# User.net
KiCad netlist of a schematic drawn in Altium Designer
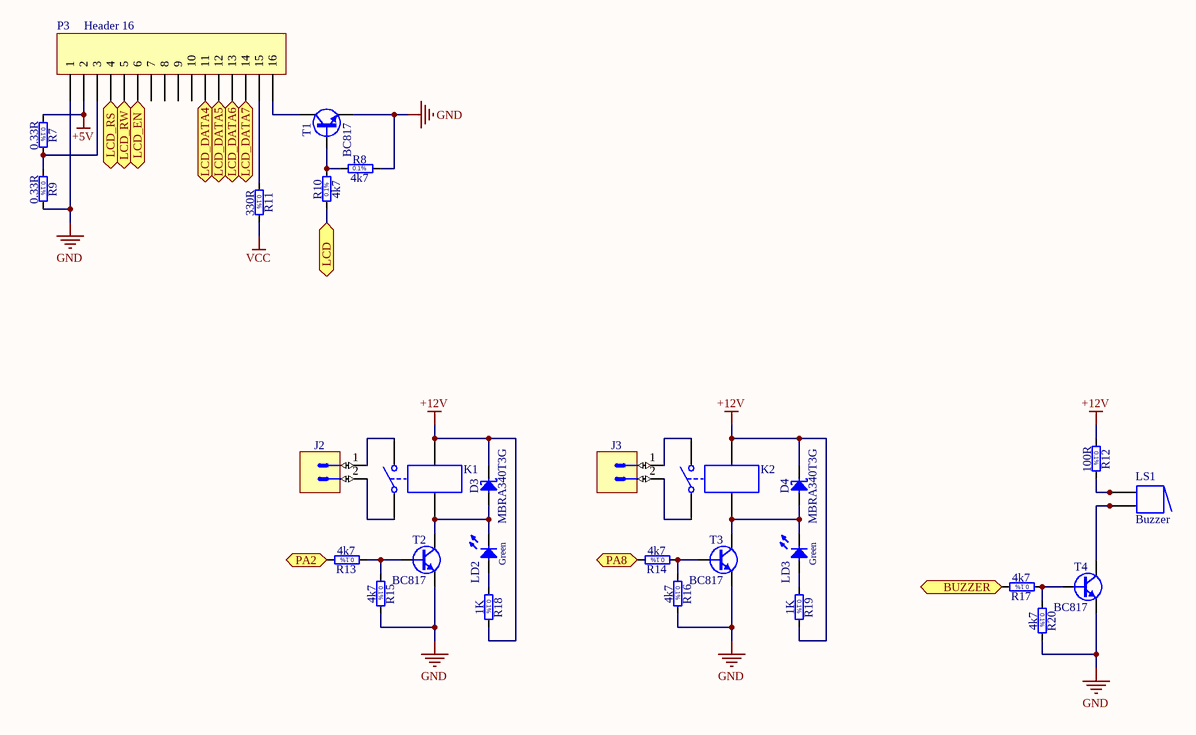
[diagram p0: User.SchDoc]

(export (version "E")
  (design (tool "Eeschema 10.0.6"))
  (components
    (comp (ref "D3")
      (value "MBRA340T3G")
      (footprint "DIOM5226X220N")
      (description "Schottky Diode")
      (fields
        (field (name "VOLTAGE") "40V")
        (field (name "POWER") "3A")
        (field (name "AUTHOR") "CERN DEM JLC")
      )
      (libsource (lib "ICs And Semiconductors") (part "Diode Schottky"))
    )
    (comp (ref "D4")
      (value "MBRA340T3G")
      (footprint "DIOM5226X220N")
      (description "Schottky Diode")
      (fields
        (field (name "VOLTAGE") "40V")
        (field (name "POWER") "3A")
        (field (name "AUTHOR") "CERN DEM JLC")
      )
      (libsource (lib "ICs And Semiconductors") (part "Diode Schottky"))
    )
    (comp (ref "J2")
      (value "~")
      (footprint "PHOENIX_1757242")
      (description "Connector 2 Male")
      (fields
        (field (name "PART NUMBER") "PHOENIX_1757242")
        (field (name "MANUFACTURER") "PHOENIX CONTACT")
        (field (name "AUTHOR") "CERN DEM JLC")
      )
      (libsource (lib "Connectors") (part "Connector 2 Male"))
    )
    (comp (ref "J3")
      (value "~")
      (footprint "PHOENIX_1757242")
      (description "Connector 2 Male")
      (fields
        (field (name "PART NUMBER") "PHOENIX_1757242")
        (field (name "MANUFACTURER") "PHOENIX CONTACT")
        (field (name "AUTHOR") "CERN DEM JLC")
      )
      (libsource (lib "Connectors") (part "Connector 2 Male"))
    )
    (comp (ref "K1")
      (value "Relay-SPST")
      (footprint "REL_FINDER_32.22.X.XXX.X300")
      (description "Single-Pole Single-Throw Relay")
      (fields (field (name "PUBLISHER") "Altium Limited"))
      (libsource (lib "Miscellaneous Devices") (part "Relay-SPST"))
    )
    (comp (ref "K2")
      (value "Relay-SPST")
      (footprint "REL_FINDER_32.22.X.XXX.X300")
      (description "Single-Pole Single-Throw Relay")
      (fields (field (name "PUBLISHER") "Altium Limited"))
      (libsource (lib "Miscellaneous Devices") (part "Relay-SPST"))
    )
    (comp (ref "LD2")
      (value "Green")
      (footprint "LED_OSRAM_LGR971")
      (description "LED Green 1C 2A")
      (fields
        (field (name "PART NUMBER") "LED_OSRAM_LGR971")
        (field (name "MANUFACTURER") "OSRAM")
        (field (name "AUTHOR") "CERN DEM JLC")
      )
      (libsource (lib "ICs And Semiconductors") (part "LED Green 1C 2A"))
    )
    (comp (ref "LD3")
      (value "Green")
      (footprint "LED_OSRAM_LGR971")
      (description "LED Green 1C 2A")
      (fields
        (field (name "PART NUMBER") "LED_OSRAM_LGR971")
        (field (name "MANUFACTURER") "OSRAM")
        (field (name "AUTHOR") "CERN DEM JLC")
      )
      (libsource (lib "ICs And Semiconductors") (part "LED Green 1C 2A"))
    )
    (comp (ref "LS1")
      (value "Buzzer")
      (footprint "ABSM-1574")
      (description "Magnetic Transducer Buzzer")
      (fields (field (name "PUBLISHER") "Altium Limited"))
      (libsource (lib "Miscellaneous Devices") (part "Buzzer"))
    )
    (comp (ref "P3")
      (value "Header 16")
      (footprint "HDR1X16")
      (description "Header, 16-Pin")
      (fields (field (name "PUBLISHER") "Altium Limited"))
      (libsource (lib "Miscellaneous Connectors") (part "Header 16"))
    )
    (comp (ref "R7")
      (value "0.33R")
      (footprint "RESC2012X60N")
      (description "Resistor - 0.1%")
      (fields
        (field (name "PART NUMBER") "R0805_1K1_0.1%_0.1W_10PPM")
        (field (name "POWER") "0.1W")
        (field (name "AUTHOR") "CERN DEM JLC")
      )
      (libsource (lib "Resistors") (part "Resistor - 0.1%"))
    )
    (comp (ref "R8")
      (value "4k7")
      (footprint "RESC2012X60N")
      (description "Resistor - 0.1%")
      (fields
        (field (name "PART NUMBER") "R0805_1K1_0.1%_0.1W_10PPM")
        (field (name "POWER") "0.1W")
        (field (name "AUTHOR") "CERN DEM JLC")
      )
      (libsource (lib "Resistors") (part "Resistor - 0.1%"))
    )
    (comp (ref "R9")
      (value "0.33R")
      (footprint "RESC2012X60N")
      (description "Resistor - 0.1%")
      (fields
        (field (name "PART NUMBER") "R0805_1K1_0.1%_0.1W_10PPM")
        (field (name "POWER") "0.1W")
        (field (name "AUTHOR") "CERN DEM JLC")
      )
      (libsource (lib "Resistors") (part "Resistor - 0.1%"))
    )
    (comp (ref "R10")
      (value "4k7")
      (footprint "RESC2012X60N")
      (description "Resistor - 0.1%")
      (fields
        (field (name "PART NUMBER") "R0805_1K1_0.1%_0.1W_10PPM")
        (field (name "POWER") "0.1W")
        (field (name "AUTHOR") "CERN DEM JLC")
      )
      (libsource (lib "Resistors") (part "Resistor - 0.1%"))
    )
    (comp (ref "R11")
      (value "330R")
      (footprint "RESC2012X60N")
      (description "Resistor - 0.1%")
      (fields
        (field (name "PART NUMBER") "R0805_1K1_0.1%_0.1W_10PPM")
        (field (name "POWER") "0.1W")
        (field (name "AUTHOR") "CERN DEM JLC")
      )
      (libsource (lib "Resistors") (part "Resistor - 0.1%"))
    )
    (comp (ref "R12")
      (value "100R")
      (footprint "RESC2012X60N")
      (description "Resistor - 0.1%")
      (fields
        (field (name "PART NUMBER") "R0805_1K1_0.1%_0.1W_10PPM")
        (field (name "POWER") "0.1W")
        (field (name "AUTHOR") "CERN DEM JLC")
      )
      (libsource (lib "Resistors") (part "Resistor - 0.1%"))
    )
    (comp (ref "R13")
      (value "4k7")
      (footprint "RESC2012X60N")
      (description "Resistor - 0.1%")
      (fields
        (field (name "PART NUMBER") "R0805_1K1_0.1%_0.1W_10PPM")
        (field (name "POWER") "0.1W")
        (field (name "AUTHOR") "CERN DEM JLC")
      )
      (libsource (lib "Resistors") (part "Resistor - 0.1%"))
    )
    (comp (ref "R14")
      (value "4k7")
      (footprint "RESC2012X60N")
      (description "Resistor - 0.1%")
      (fields
        (field (name "PART NUMBER") "R0805_1K1_0.1%_0.1W_10PPM")
        (field (name "POWER") "0.1W")
        (field (name "AUTHOR") "CERN DEM JLC")
      )
      (libsource (lib "Resistors") (part "Resistor - 0.1%"))
    )
    (comp (ref "R15")
      (value "4k7")
      (footprint "RESC2012X60N")
      (description "Resistor - 0.1%")
      (fields
        (field (name "PART NUMBER") "R0805_1K1_0.1%_0.1W_10PPM")
        (field (name "POWER") "0.1W")
        (field (name "AUTHOR") "CERN DEM JLC")
      )
      (libsource (lib "Resistors") (part "Resistor - 0.1%"))
    )
    (comp (ref "R16")
      (value "4k7")
      (footprint "RESC2012X60N")
      (description "Resistor - 0.1%")
      (fields
        (field (name "PART NUMBER") "R0805_1K1_0.1%_0.1W_10PPM")
        (field (name "POWER") "0.1W")
        (field (name "AUTHOR") "CERN DEM JLC")
      )
      (libsource (lib "Resistors") (part "Resistor - 0.1%"))
    )
    (comp (ref "R17")
      (value "4k7")
      (footprint "RESC2012X60N")
      (description "Resistor - 0.1%")
      (fields
        (field (name "PART NUMBER") "R0805_1K1_0.1%_0.1W_10PPM")
        (field (name "POWER") "0.1W")
        (field (name "AUTHOR") "CERN DEM JLC")
      )
      (libsource (lib "Resistors") (part "Resistor - 0.1%"))
    )
    (comp (ref "R18")
      (value "1K")
      (footprint "RESC2012X60N")
      (description "Resistor - 0.1%")
      (fields
        (field (name "PART NUMBER") "R0805_1K1_0.1%_0.1W_10PPM")
        (field (name "POWER") "0.1W")
        (field (name "AUTHOR") "CERN DEM JLC")
      )
      (libsource (lib "Resistors") (part "Resistor - 0.1%"))
    )
    (comp (ref "R19")
      (value "1K")
      (footprint "RESC2012X60N")
      (description "Resistor - 0.1%")
      (fields
        (field (name "PART NUMBER") "R0805_1K1_0.1%_0.1W_10PPM")
        (field (name "POWER") "0.1W")
        (field (name "AUTHOR") "CERN DEM JLC")
      )
      (libsource (lib "Resistors") (part "Resistor - 0.1%"))
    )
    (comp (ref "R20")
      (value "4k7")
      (footprint "RESC2012X60N")
      (description "Resistor - 0.1%")
      (fields
        (field (name "PART NUMBER") "R0805_1K1_0.1%_0.1W_10PPM")
        (field (name "POWER") "0.1W")
        (field (name "AUTHOR") "CERN DEM JLC")
      )
      (libsource (lib "Resistors") (part "Resistor - 0.1%"))
    )
    (comp (ref "T1")
      (value "BC817")
      (footprint "SOT95P230X110-3N")
      (description "NPN Transistor")
      (fields (field (name "MANUFACTURER") "NXP SEMICONDUCTORS") (field (name "AUTHOR") "CERN DEM JLC"))
      (libsource (lib "ICs And Semiconductors") (part "NPN B1 E2 C3"))
    )
    (comp (ref "T2")
      (value "BC817")
      (footprint "SOT95P230X110-3N")
      (description "NPN Transistor")
      (fields (field (name "MANUFACTURER") "NXP SEMICONDUCTORS") (field (name "AUTHOR") "CERN DEM JLC"))
      (libsource (lib "ICs And Semiconductors") (part "NPN B1 E2 C3"))
    )
    (comp (ref "T3")
      (value "BC817")
      (footprint "SOT95P230X110-3N")
      (description "NPN Transistor")
      (fields (field (name "MANUFACTURER") "NXP SEMICONDUCTORS") (field (name "AUTHOR") "CERN DEM JLC"))
      (libsource (lib "ICs And Semiconductors") (part "NPN B1 E2 C3"))
    )
    (comp (ref "T4")
      (value "BC817")
      (footprint "SOT95P230X110-3N")
      (description "NPN Transistor")
      (fields (field (name "MANUFACTURER") "NXP SEMICONDUCTORS") (field (name "AUTHOR") "CERN DEM JLC"))
      (libsource (lib "ICs And Semiconductors") (part "NPN B1 E2 C3"))
    )
  )
  (nets
    (net (code "1") (name "+5V") (class "Default")
      (node (ref "P3") (pin "2") (pinfunction "2_2") (pintype "passive"))
      (node (ref "R7") (pin "1") (pinfunction "1_1") (pintype "passive"))
    )
    (net (code "2") (name "+12V") (class "Default")
      (node (ref "D3") (pin "1") (pinfunction "C_1") (pintype "passive"))
      (node (ref "D4") (pin "1") (pinfunction "C_1") (pintype "passive"))
      (node (ref "K1") (pin "4") (pinfunction "4_4") (pintype "passive"))
      (node (ref "K2") (pin "4") (pinfunction "4_4") (pintype "passive"))
      (node (ref "R12") (pin "1") (pinfunction "1_1") (pintype "passive"))
      (node (ref "R18") (pin "2") (pinfunction "2_2") (pintype "passive"))
      (node (ref "R19") (pin "2") (pinfunction "2_2") (pintype "passive"))
    )
    (net (code "3") (name "/BUZZER") (class "Default")
      (node (ref "R17") (pin "2") (pinfunction "2_2") (pintype "passive"))
    )
    (net (code "4") (name "/LCD") (class "Default")
      (node (ref "R10") (pin "1") (pinfunction "1_1") (pintype "passive"))
    )
    (net (code "5") (name "/LCD_DATA4") (class "Default")
      (node (ref "P3") (pin "11") (pinfunction "11_11") (pintype "passive"))
    )
    (net (code "6") (name "/LCD_DATA5") (class "Default")
      (node (ref "P3") (pin "12") (pinfunction "12_12") (pintype "passive"))
    )
    (net (code "7") (name "/LCD_DATA6") (class "Default")
      (node (ref "P3") (pin "13") (pinfunction "13_13") (pintype "passive"))
    )
    (net (code "8") (name "/LCD_DATA7") (class "Default")
      (node (ref "P3") (pin "14") (pinfunction "14_14") (pintype "passive"))
    )
    (net (code "9") (name "/LCD_EN") (class "Default")
      (node (ref "P3") (pin "6") (pinfunction "6_6") (pintype "passive"))
    )
    (net (code "10") (name "/LCD_RS") (class "Default")
      (node (ref "P3") (pin "4") (pinfunction "4_4") (pintype "passive"))
    )
    (net (code "11") (name "/LCD_RW") (class "Default")
      (node (ref "P3") (pin "5") (pinfunction "5_5") (pintype "passive"))
    )
    (net (code "12") (name "/PA2") (class "Default")
      (node (ref "R13") (pin "2") (pinfunction "2_2") (pintype "passive"))
    )
    (net (code "13") (name "/PA8") (class "Default")
      (node (ref "R14") (pin "2") (pinfunction "2_2") (pintype "passive"))
    )
    (net (code "14") (name "GND") (class "Default")
      (node (ref "P3") (pin "1") (pinfunction "1_1") (pintype "passive"))
      (node (ref "R15") (pin "2") (pinfunction "2_2") (pintype "passive"))
      (node (ref "R16") (pin "2") (pinfunction "2_2") (pintype "passive"))
      (node (ref "R20") (pin "2") (pinfunction "2_2") (pintype "passive"))
      (node (ref "R8") (pin "2") (pinfunction "2_2") (pintype "passive"))
      (node (ref "R9") (pin "2") (pinfunction "2_2") (pintype "passive"))
      (node (ref "T1") (pin "2") (pinfunction "E_2") (pintype "passive"))
      (node (ref "T2") (pin "2") (pinfunction "E_2") (pintype "passive"))
      (node (ref "T3") (pin "2") (pinfunction "E_2") (pintype "passive"))
      (node (ref "T4") (pin "2") (pinfunction "E_2") (pintype "passive"))
    )
    (net (code "15") (name "Net-(D3-A)") (class "Default")
      (node (ref "D3") (pin "2") (pinfunction "A_2") (pintype "passive"))
      (node (ref "K1") (pin "3") (pinfunction "3_3") (pintype "passive"))
      (node (ref "LD2") (pin "1") (pinfunction "C_1") (pintype "passive"))
      (node (ref "T2") (pin "3") (pinfunction "C_3") (pintype "passive"))
    )
    (net (code "16") (name "Net-(D4-A)") (class "Default")
      (node (ref "D4") (pin "2") (pinfunction "A_2") (pintype "passive"))
      (node (ref "K2") (pin "3") (pinfunction "3_3") (pintype "passive"))
      (node (ref "LD3") (pin "1") (pinfunction "C_1") (pintype "passive"))
      (node (ref "T3") (pin "3") (pinfunction "C_3") (pintype "passive"))
    )
    (net (code "17") (name "Net-(J2-Pad1)") (class "Default")
      (node (ref "J2") (pin "1") (pinfunction "1_1") (pintype "bidirectional"))
      (node (ref "K1") (pin "2") (pinfunction "2_2") (pintype "passive"))
    )
    (net (code "18") (name "Net-(J2-Pad2)") (class "Default")
      (node (ref "J2") (pin "2") (pinfunction "2_2") (pintype "bidirectional"))
      (node (ref "K1") (pin "1") (pinfunction "1_1") (pintype "passive"))
    )
    (net (code "19") (name "Net-(J3-Pad1)") (class "Default")
      (node (ref "J3") (pin "1") (pinfunction "1_1") (pintype "bidirectional"))
      (node (ref "K2") (pin "2") (pinfunction "2_2") (pintype "passive"))
    )
    (net (code "20") (name "Net-(J3-Pad2)") (class "Default")
      (node (ref "J3") (pin "2") (pinfunction "2_2") (pintype "bidirectional"))
      (node (ref "K2") (pin "1") (pinfunction "1_1") (pintype "passive"))
    )
    (net (code "21") (name "Net-(LD2-A)") (class "Default")
      (node (ref "LD2") (pin "2") (pinfunction "A_2") (pintype "passive"))
      (node (ref "R18") (pin "1") (pinfunction "1_1") (pintype "passive"))
    )
    (net (code "22") (name "Net-(LD3-A)") (class "Default")
      (node (ref "LD3") (pin "2") (pinfunction "A_2") (pintype "passive"))
      (node (ref "R19") (pin "1") (pinfunction "1_1") (pintype "passive"))
    )
    (net (code "23") (name "Net-(LS1-Pad1)") (class "Default")
      (node (ref "LS1") (pin "1") (pinfunction "1_1") (pintype "passive"))
      (node (ref "LS1") (pin "1A") (pinfunction "1A_1A") (pintype "passive"))
      (node (ref "R12") (pin "2") (pinfunction "2_2") (pintype "passive"))
    )
    (net (code "24") (name "Net-(P3-Pad3)") (class "Default")
      (node (ref "P3") (pin "3") (pinfunction "3_3") (pintype "passive"))
      (node (ref "R7") (pin "2") (pinfunction "2_2") (pintype "passive"))
      (node (ref "R9") (pin "1") (pinfunction "1_1") (pintype "passive"))
    )
    (net (code "25") (name "Net-(P3-Pad15)") (class "Default")
      (node (ref "P3") (pin "15") (pinfunction "15_15") (pintype "passive"))
      (node (ref "R11") (pin "1") (pinfunction "1_1") (pintype "passive"))
    )
    (net (code "26") (name "Net-(T1-B)") (class "Default")
      (node (ref "R10") (pin "2") (pinfunction "2_2") (pintype "passive"))
      (node (ref "R8") (pin "1") (pinfunction "1_1") (pintype "passive"))
      (node (ref "T1") (pin "1") (pinfunction "B_1") (pintype "passive"))
    )
    (net (code "27") (name "Net-(T1-C)") (class "Default")
      (node (ref "P3") (pin "16") (pinfunction "16_16") (pintype "passive"))
      (node (ref "T1") (pin "3") (pinfunction "C_3") (pintype "passive"))
    )
    (net (code "28") (name "Net-(T2-B)") (class "Default")
      (node (ref "R13") (pin "1") (pinfunction "1_1") (pintype "passive"))
      (node (ref "R15") (pin "1") (pinfunction "1_1") (pintype "passive"))
      (node (ref "T2") (pin "1") (pinfunction "B_1") (pintype "passive"))
    )
    (net (code "29") (name "Net-(T3-B)") (class "Default")
      (node (ref "R14") (pin "1") (pinfunction "1_1") (pintype "passive"))
      (node (ref "R16") (pin "1") (pinfunction "1_1") (pintype "passive"))
      (node (ref "T3") (pin "1") (pinfunction "B_1") (pintype "passive"))
    )
    (net (code "30") (name "Net-(T4-B)") (class "Default")
      (node (ref "R17") (pin "1") (pinfunction "1_1") (pintype "passive"))
      (node (ref "R20") (pin "1") (pinfunction "1_1") (pintype "passive"))
      (node (ref "T4") (pin "1") (pinfunction "B_1") (pintype "passive"))
    )
    (net (code "31") (name "Net-(T4-C)") (class "Default")
      (node (ref "LS1") (pin "2") (pinfunction "2_2") (pintype "passive"))
      (node (ref "LS1") (pin "2A") (pinfunction "2A_2A") (pintype "passive"))
      (node (ref "T4") (pin "3") (pinfunction "C_3") (pintype "passive"))
    )
    (net (code "32") (name "VCC") (class "Default")
      (node (ref "R11") (pin "2") (pinfunction "2_2") (pintype "passive"))
    )
    (net (code "33") (name "unconnected-(P3-Pad7)") (class "Default")
      (node (ref "P3") (pin "7") (pinfunction "7_7") (pintype "passive"))
    )
    (net (code "34") (name "unconnected-(P3-Pad8)") (class "Default")
      (node (ref "P3") (pin "8") (pinfunction "8_8") (pintype "passive"))
    )
    (net (code "35") (name "unconnected-(P3-Pad9)") (class "Default")
      (node (ref "P3") (pin "9") (pinfunction "9_9") (pintype "passive"))
    )
    (net (code "36") (name "unconnected-(P3-Pad10)") (class "Default")
      (node (ref "P3") (pin "10") (pinfunction "10_10") (pintype "passive"))
    )
  )
)
